# top-v1_0r32.net
KiCad netlist of a schematic drawn in EAGLE
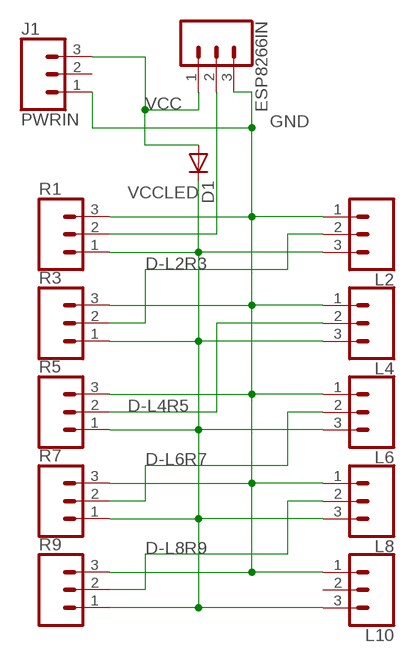
[diagram p0: schematic, sheet 1]

(export (version "E")
  (design (tool "Eeschema 10.0.6"))
  (components
    (comp (ref "D1")
      (value "1N4004")
      (footprint "eagle-import:DO41-10")
      (libsource (lib "eagle-import") (part "1N4004"))
    )
    (comp (ref "ESP8266IN")
      (value "CONN_03")
      (footprint "eagle-import:1X03")
      (libsource (lib "eagle-import") (part "CONN_03"))
    )
    (comp (ref "J1")
      (value "PWRIN")
      (footprint "eagle-import:1X03")
      (libsource (lib "eagle-import") (part "CONN_03"))
    )
    (comp (ref "L2")
      (value "CONN_03")
      (footprint "eagle-import:1X03")
      (libsource (lib "eagle-import") (part "SparkFun-Connectors_513_CONN_03"))
    )
    (comp (ref "L4")
      (value "CONN_03")
      (footprint "eagle-import:1X03")
      (libsource (lib "eagle-import") (part "SparkFun-Connectors_513_CONN_03"))
    )
    (comp (ref "L6")
      (value "CONN_03")
      (footprint "eagle-import:1X03")
      (libsource (lib "eagle-import") (part "SparkFun-Connectors_513_CONN_03"))
    )
    (comp (ref "L8")
      (value "CONN_03")
      (footprint "eagle-import:1X03")
      (libsource (lib "eagle-import") (part "SparkFun-Connectors_513_CONN_03"))
    )
    (comp (ref "L10")
      (value "CONN_03")
      (footprint "eagle-import:1X03")
      (libsource (lib "eagle-import") (part "SparkFun-Connectors_513_CONN_03"))
    )
    (comp (ref "R1")
      (value "CONN_03")
      (footprint "eagle-import:1X03")
      (libsource (lib "eagle-import") (part "SparkFun-Connectors_513_CONN_03"))
    )
    (comp (ref "R3")
      (value "CONN_03")
      (footprint "eagle-import:1X03")
      (libsource (lib "eagle-import") (part "SparkFun-Connectors_513_CONN_03"))
    )
    (comp (ref "R5")
      (value "CONN_03")
      (footprint "eagle-import:1X03")
      (libsource (lib "eagle-import") (part "SparkFun-Connectors_513_CONN_03"))
    )
    (comp (ref "R7")
      (value "CONN_03")
      (footprint "eagle-import:1X03")
      (libsource (lib "eagle-import") (part "SparkFun-Connectors_513_CONN_03"))
    )
    (comp (ref "R9")
      (value "CONN_03")
      (footprint "eagle-import:1X03")
      (libsource (lib "eagle-import") (part "SparkFun-Connectors_513_CONN_03"))
    )
  )
  (nets
    (net (code "1") (name "/D-L2R3") (class "Default")
      (node (ref "L2") (pin "2") (pinfunction "2_2") (pintype "passive"))
      (node (ref "R3") (pin "2") (pinfunction "2_2") (pintype "passive"))
    )
    (net (code "2") (name "/D-L4R5") (class "Default")
      (node (ref "L4") (pin "2") (pinfunction "2_2") (pintype "passive"))
      (node (ref "R5") (pin "2") (pinfunction "2_2") (pintype "passive"))
    )
    (net (code "3") (name "/D-L6R7") (class "Default")
      (node (ref "L6") (pin "2") (pinfunction "2_2") (pintype "passive"))
      (node (ref "R7") (pin "2") (pinfunction "2_2") (pintype "passive"))
    )
    (net (code "4") (name "/D-L8R9") (class "Default")
      (node (ref "L8") (pin "2") (pinfunction "2_2") (pintype "passive"))
      (node (ref "R9") (pin "2") (pinfunction "2_2") (pintype "passive"))
    )
    (net (code "5") (name "/GND") (class "Default")
      (node (ref "ESP8266IN") (pin "3") (pinfunction "3_3") (pintype "passive"))
      (node (ref "J1") (pin "1") (pinfunction "1_1") (pintype "passive"))
      (node (ref "L10") (pin "1") (pinfunction "1_1") (pintype "passive"))
      (node (ref "L2") (pin "1") (pinfunction "1_1") (pintype "passive"))
      (node (ref "L4") (pin "1") (pinfunction "1_1") (pintype "passive"))
      (node (ref "L6") (pin "1") (pinfunction "1_1") (pintype "passive"))
      (node (ref "L8") (pin "1") (pinfunction "1_1") (pintype "passive"))
      (node (ref "R1") (pin "3") (pinfunction "3_3") (pintype "passive"))
      (node (ref "R3") (pin "3") (pinfunction "3_3") (pintype "passive"))
      (node (ref "R5") (pin "3") (pinfunction "3_3") (pintype "passive"))
      (node (ref "R7") (pin "3") (pinfunction "3_3") (pintype "passive"))
      (node (ref "R9") (pin "3") (pinfunction "3_3") (pintype "passive"))
    )
    (net (code "6") (name "/VCC") (class "Default")
      (node (ref "D1") (pin "A") (pinfunction "A_A") (pintype "passive"))
      (node (ref "ESP8266IN") (pin "1") (pinfunction "1_1") (pintype "passive"))
      (node (ref "J1") (pin "3") (pinfunction "3_3") (pintype "passive"))
    )
    (net (code "7") (name "/VCCLED") (class "Default")
      (node (ref "D1") (pin "C") (pinfunction "C_C") (pintype "passive"))
      (node (ref "L10") (pin "3") (pinfunction "3_3") (pintype "passive"))
      (node (ref "L2") (pin "3") (pinfunction "3_3") (pintype "passive"))
      (node (ref "L4") (pin "3") (pinfunction "3_3") (pintype "passive"))
      (node (ref "L6") (pin "3") (pinfunction "3_3") (pintype "passive"))
      (node (ref "L8") (pin "3") (pinfunction "3_3") (pintype "passive"))
      (node (ref "R1") (pin "1") (pinfunction "1_1") (pintype "passive"))
      (node (ref "R3") (pin "1") (pinfunction "1_1") (pintype "passive"))
      (node (ref "R5") (pin "1") (pinfunction "1_1") (pintype "passive"))
      (node (ref "R7") (pin "1") (pinfunction "1_1") (pintype "passive"))
      (node (ref "R9") (pin "1") (pinfunction "1_1") (pintype "passive"))
    )
    (net (code "8") (name "Net-(ESP8266IN-Pad2)") (class "Default")
      (node (ref "ESP8266IN") (pin "2") (pinfunction "2_2") (pintype "passive"))
      (node (ref "R1") (pin "2") (pinfunction "2_2") (pintype "passive"))
    )
    (net (code "9") (name "unconnected-(J1-Pad2)") (class "Default")
      (node (ref "J1") (pin "2") (pinfunction "2_2") (pintype "passive"))
    )
    (net (code "10") (name "unconnected-(L10-Pad2)") (class "Default")
      (node (ref "L10") (pin "2") (pinfunction "2_2") (pintype "passive"))
    )
  )
)
